# encode_and_decode_2.net
KiCad netlist of a schematic drawn in Altium Designer
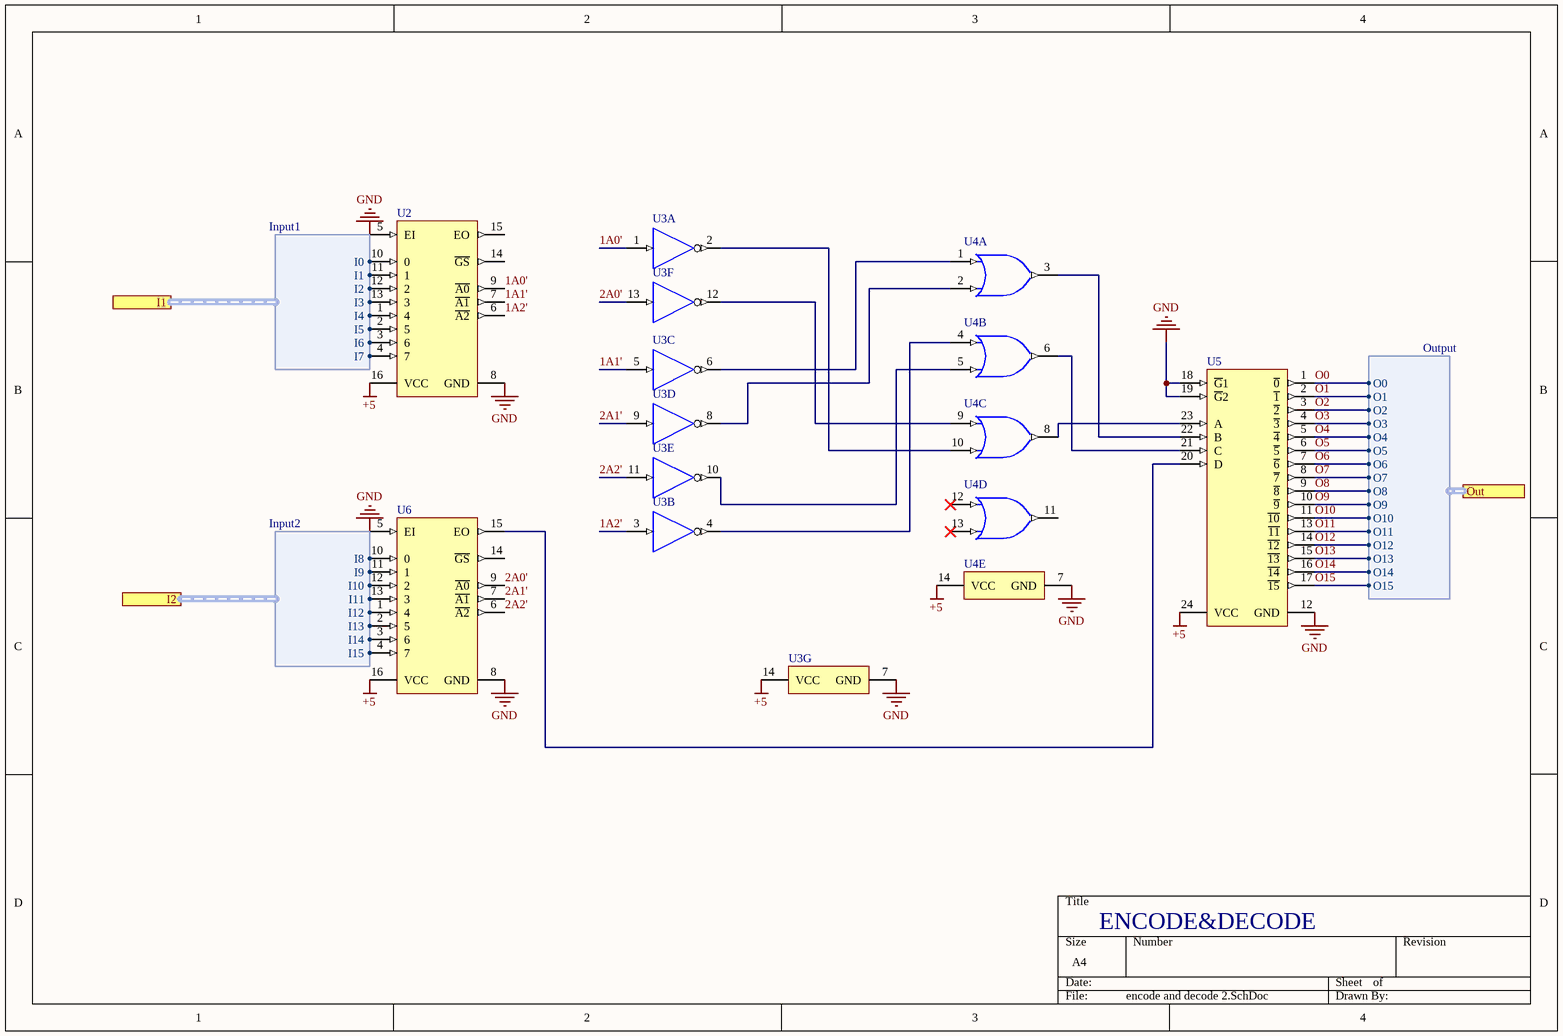
[diagram p0: encode and decode 2.SchDoc]

(export (version "E")
  (design (tool "Eeschema 10.0.6"))
  (components
    (comp (ref "U2")
      (value "SN74LS148N")
      (footprint "N0016A")
      (description "8-line to 3-line priority encoder, N0016A, TUBE")
      (fields
        (field (name "GENERIC PART NUMBER") "SN74LS148")
        (field (name "MANUFACTURER") "Texas Instruments")
      )
      (libsource (lib "Altium Content Vault") (part "TI-SNX4XX148-16"))
    )
    (comp (ref "U3")
      (value "SN74HCU04N")
      (footprint "N0014A")
      (description "Hex Inverters, N0014A, TUBE")
      (fields
        (field (name "MANUFACTURER") "Texas Instruments")
        (field (name "GENERIC PART NUMBER") "SN74HCU04")
      )
      (libsource (lib "Altium Content Vault") (part "TI-CD_SNX4XXXXXX4X_19A-14"))
    )
    (comp (ref "U4")
      (value "SN7432N")
      (footprint "N0014A")
      (description "Quad 2-input positive-OR gates, N0014A, TUBE")
      (fields (field (name "MANUFACTURER") "Texas Instruments") (field (name "GENERIC PART NUMBER") "SN7432"))
      (libsource (lib "Altium Content Vault") (part "TI-OR-4-2IN-14"))
    )
    (comp (ref "U5")
      (value "SN74154N")
      (footprint "N0024A")
      (description "4-Line To 16-Line Decoders/Demultiplexers, N0024A, TUBE")
      (fields
        (field (name "GENERIC PART NUMBER") "SN74154")
        (field (name "MANUFACTURER") "Texas Instruments")
      )
      (libsource (lib "Altium Content Vault") (part "TI-SN54_74154-24"))
    )
    (comp (ref "U6")
      (value "SN74LS148N")
      (footprint "N0016A")
      (description "8-line to 3-line priority encoder, N0016A, TUBE")
      (fields
        (field (name "GENERIC PART NUMBER") "SN74LS148")
        (field (name "MANUFACTURER") "Texas Instruments")
      )
      (libsource (lib "Altium Content Vault") (part "TI-SNX4XX148-16"))
    )
  )
  (nets
    (net (code "4") (name "+5") (class "Default")
      (node (ref "U2") (pin "16") (pinfunction "VCC_16") (pintype "power_in"))
      (node (ref "U3") (pin "14") (pinfunction "VCC_14") (pintype "power_in"))
      (node (ref "U4") (pin "14") (pinfunction "VCC_14") (pintype "power_in"))
      (node (ref "U5") (pin "24") (pinfunction "VCC_24") (pintype "power_in"))
      (node (ref "U6") (pin "16") (pinfunction "VCC_16") (pintype "power_in"))
    )
    (net (code "5") (name "/1A0'") (class "Default")
      (node (ref "U2") (pin "9") (pinfunction "~{A0}_9") (pintype "output"))
      (node (ref "U3") (pin "1") (pinfunction "1A_1") (pintype "input"))
    )
    (net (code "6") (name "/1A1'") (class "Default")
      (node (ref "U2") (pin "7") (pinfunction "~{A1}_7") (pintype "output"))
      (node (ref "U3") (pin "5") (pinfunction "3A_5") (pintype "input"))
    )
    (net (code "7") (name "/1A2'") (class "Default")
      (node (ref "U2") (pin "6") (pinfunction "~{A2}_6") (pintype "output"))
      (node (ref "U3") (pin "3") (pinfunction "2A_3") (pintype "input"))
    )
    (net (code "8") (name "/2A0'") (class "Default")
      (node (ref "U3") (pin "13") (pinfunction "6A_13") (pintype "input"))
      (node (ref "U6") (pin "9") (pinfunction "~{A0}_9") (pintype "output"))
    )
    (net (code "9") (name "/2A1'") (class "Default")
      (node (ref "U3") (pin "9") (pinfunction "4A_9") (pintype "input"))
      (node (ref "U6") (pin "7") (pinfunction "~{A1}_7") (pintype "output"))
    )
    (net (code "10") (name "/2A2'") (class "Default")
      (node (ref "U3") (pin "11") (pinfunction "5A_11") (pintype "input"))
      (node (ref "U6") (pin "6") (pinfunction "~{A2}_6") (pintype "output"))
    )
    (net (code "11") (name "/I0") (class "Default")
      (node (ref "U2") (pin "10") (pinfunction "0_10") (pintype "input"))
    )
    (net (code "12") (name "/I3") (class "Default")
      (node (ref "U2") (pin "13") (pinfunction "3_13") (pintype "input"))
    )
    (net (code "13") (name "/I4") (class "Default")
      (node (ref "U2") (pin "1") (pinfunction "4_1") (pintype "input"))
    )
    (net (code "14") (name "/I5") (class "Default")
      (node (ref "U2") (pin "2") (pinfunction "5_2") (pintype "input"))
    )
    (net (code "15") (name "/I6") (class "Default")
      (node (ref "U2") (pin "3") (pinfunction "6_3") (pintype "input"))
    )
    (net (code "16") (name "/I7") (class "Default")
      (node (ref "U2") (pin "4") (pinfunction "7_4") (pintype "input"))
    )
    (net (code "17") (name "/I8") (class "Default")
      (node (ref "U6") (pin "10") (pinfunction "0_10") (pintype "input"))
    )
    (net (code "18") (name "/I9") (class "Default")
      (node (ref "U6") (pin "11") (pinfunction "1_11") (pintype "input"))
    )
    (net (code "19") (name "/I10") (class "Default")
      (node (ref "U6") (pin "12") (pinfunction "2_12") (pintype "input"))
    )
    (net (code "20") (name "/I11") (class "Default")
      (node (ref "U6") (pin "13") (pinfunction "3_13") (pintype "input"))
    )
    (net (code "21") (name "/I12") (class "Default")
      (node (ref "U6") (pin "1") (pinfunction "4_1") (pintype "input"))
    )
    (net (code "22") (name "/I13") (class "Default")
      (node (ref "U6") (pin "2") (pinfunction "5_2") (pintype "input"))
    )
    (net (code "23") (name "/I14") (class "Default")
      (node (ref "U6") (pin "3") (pinfunction "6_3") (pintype "input"))
    )
    (net (code "24") (name "/I15") (class "Default")
      (node (ref "U6") (pin "4") (pinfunction "7_4") (pintype "input"))
    )
    (net (code "25") (name "/O0") (class "Default")
      (node (ref "U5") (pin "1") (pinfunction "~{0}_1") (pintype "output"))
    )
    (net (code "26") (name "/O1") (class "Default")
      (node (ref "U5") (pin "2") (pinfunction "~{1}_2") (pintype "output"))
    )
    (net (code "27") (name "/O2") (class "Default")
      (node (ref "U5") (pin "3") (pinfunction "~{2}_3") (pintype "output"))
    )
    (net (code "28") (name "/O3") (class "Default")
      (node (ref "U5") (pin "4") (pinfunction "~{3}_4") (pintype "output"))
    )
    (net (code "29") (name "/O4") (class "Default")
      (node (ref "U5") (pin "5") (pinfunction "~{4}_5") (pintype "output"))
    )
    (net (code "30") (name "/O5") (class "Default")
      (node (ref "U5") (pin "6") (pinfunction "~{5}_6") (pintype "output"))
    )
    (net (code "31") (name "/O6") (class "Default")
      (node (ref "U5") (pin "7") (pinfunction "~{6}_7") (pintype "output"))
    )
    (net (code "32") (name "/O7") (class "Default")
      (node (ref "U5") (pin "8") (pinfunction "~{7}_8") (pintype "output"))
    )
    (net (code "33") (name "/O8") (class "Default")
      (node (ref "U5") (pin "9") (pinfunction "~{8}_9") (pintype "output"))
    )
    (net (code "34") (name "/O9") (class "Default")
      (node (ref "U5") (pin "10") (pinfunction "~{9}_10") (pintype "output"))
    )
    (net (code "35") (name "/O10") (class "Default")
      (node (ref "U5") (pin "11") (pinfunction "~{10}_11") (pintype "output"))
    )
    (net (code "36") (name "/O11") (class "Default")
      (node (ref "U5") (pin "13") (pinfunction "~{11}_13") (pintype "output"))
    )
    (net (code "37") (name "/O12") (class "Default")
      (node (ref "U5") (pin "14") (pinfunction "~{12}_14") (pintype "output"))
    )
    (net (code "38") (name "/O13") (class "Default")
      (node (ref "U5") (pin "15") (pinfunction "~{13}_15") (pintype "output"))
    )
    (net (code "39") (name "/O14") (class "Default")
      (node (ref "U5") (pin "16") (pinfunction "~{14}_16") (pintype "output"))
    )
    (net (code "40") (name "/O15") (class "Default")
      (node (ref "U5") (pin "17") (pinfunction "~{15}_17") (pintype "output"))
    )
    (net (code "44") (name "GND") (class "Default")
      (node (ref "U2") (pin "5") (pinfunction "EI_5") (pintype "input"))
      (node (ref "U2") (pin "8") (pinfunction "GND_8") (pintype "power_in"))
      (node (ref "U3") (pin "7") (pinfunction "GND_7") (pintype "power_in"))
      (node (ref "U4") (pin "7") (pinfunction "GND_7") (pintype "power_in"))
      (node (ref "U5") (pin "12") (pinfunction "GND_12") (pintype "power_in"))
      (node (ref "U5") (pin "18") (pinfunction "~{G}1_18") (pintype "input"))
      (node (ref "U5") (pin "19") (pinfunction "~{G}2_19") (pintype "input"))
      (node (ref "U6") (pin "5") (pinfunction "EI_5") (pintype "input"))
      (node (ref "U6") (pin "8") (pinfunction "GND_8") (pintype "power_in"))
    )
    (net (code "45") (name "Net-(U3A-~{1Y})") (class "Default")
      (node (ref "U3") (pin "2") (pinfunction "~{1Y}_2") (pintype "output"))
      (node (ref "U4") (pin "10") (pinfunction "3B_10") (pintype "input"))
    )
    (net (code "46") (name "Net-(U3B-~{2Y})") (class "Default")
      (node (ref "U3") (pin "4") (pinfunction "~{2Y}_4") (pintype "output"))
      (node (ref "U4") (pin "4") (pinfunction "2A_4") (pintype "input"))
    )
    (net (code "47") (name "Net-(U3C-~{3Y})") (class "Default")
      (node (ref "U3") (pin "6") (pinfunction "~{3Y}_6") (pintype "output"))
      (node (ref "U4") (pin "1") (pinfunction "1A_1") (pintype "input"))
    )
    (net (code "48") (name "Net-(U3D-~{4Y})") (class "Default")
      (node (ref "U3") (pin "8") (pinfunction "~{4Y}_8") (pintype "output"))
      (node (ref "U4") (pin "2") (pinfunction "1B_2") (pintype "input"))
    )
    (net (code "49") (name "Net-(U3E-~{5Y})") (class "Default")
      (node (ref "U3") (pin "10") (pinfunction "~{5Y}_10") (pintype "output"))
      (node (ref "U4") (pin "5") (pinfunction "2B_5") (pintype "input"))
    )
    (net (code "50") (name "Net-(U3F-~{6Y})") (class "Default")
      (node (ref "U3") (pin "12") (pinfunction "~{6Y}_12") (pintype "output"))
      (node (ref "U4") (pin "9") (pinfunction "3A_9") (pintype "input"))
    )
    (net (code "51") (name "Net-(U4A-1Y)") (class "Default")
      (node (ref "U4") (pin "3") (pinfunction "1Y_3") (pintype "output"))
      (node (ref "U5") (pin "22") (pinfunction "B_22") (pintype "input"))
    )
    (net (code "52") (name "Net-(U4B-2Y)") (class "Default")
      (node (ref "U4") (pin "6") (pinfunction "2Y_6") (pintype "output"))
      (node (ref "U5") (pin "21") (pinfunction "C_21") (pintype "input"))
    )
    (net (code "53") (name "Net-(U4C-3Y)") (class "Default")
      (node (ref "U4") (pin "8") (pinfunction "3Y_8") (pintype "output"))
      (node (ref "U5") (pin "23") (pinfunction "A_23") (pintype "input"))
    )
    (net (code "54") (name "Net-(U5-D)") (class "Default")
      (node (ref "U5") (pin "20") (pinfunction "D_20") (pintype "input"))
      (node (ref "U6") (pin "15") (pinfunction "EO_15") (pintype "output"))
    )
    (net (code "55") (name "unconnected-(U2-1-Pad11)") (class "Default")
      (node (ref "U2") (pin "11") (pinfunction "1_11") (pintype "input"))
    )
    (net (code "56") (name "unconnected-(U2-2-Pad12)") (class "Default")
      (node (ref "U2") (pin "12") (pinfunction "2_12") (pintype "input"))
    )
    (net (code "57") (name "unconnected-(U2-EO-Pad15)") (class "Default")
      (node (ref "U2") (pin "15") (pinfunction "EO_15") (pintype "output"))
    )
    (net (code "58") (name "unconnected-(U2-~{GS}-Pad14)") (class "Default")
      (node (ref "U2") (pin "14") (pinfunction "~{GS}_14") (pintype "output"))
    )
    (net (code "59") (name "unconnected-(U4D-4A-Pad12)") (class "Default")
      (node (ref "U4") (pin "12") (pinfunction "4A_12") (pintype "input+no_connect"))
    )
    (net (code "60") (name "unconnected-(U4D-4B-Pad13)") (class "Default")
      (node (ref "U4") (pin "13") (pinfunction "4B_13") (pintype "input+no_connect"))
    )
    (net (code "61") (name "unconnected-(U4D-4Y-Pad11)") (class "Default")
      (node (ref "U4") (pin "11") (pinfunction "4Y_11") (pintype "output"))
    )
    (net (code "62") (name "unconnected-(U6-~{GS}-Pad14)") (class "Default")
      (node (ref "U6") (pin "14") (pinfunction "~{GS}_14") (pintype "output"))
    )
  )
)
